# STM32F103T8.net
KiCad netlist of a schematic drawn in Altium Designer
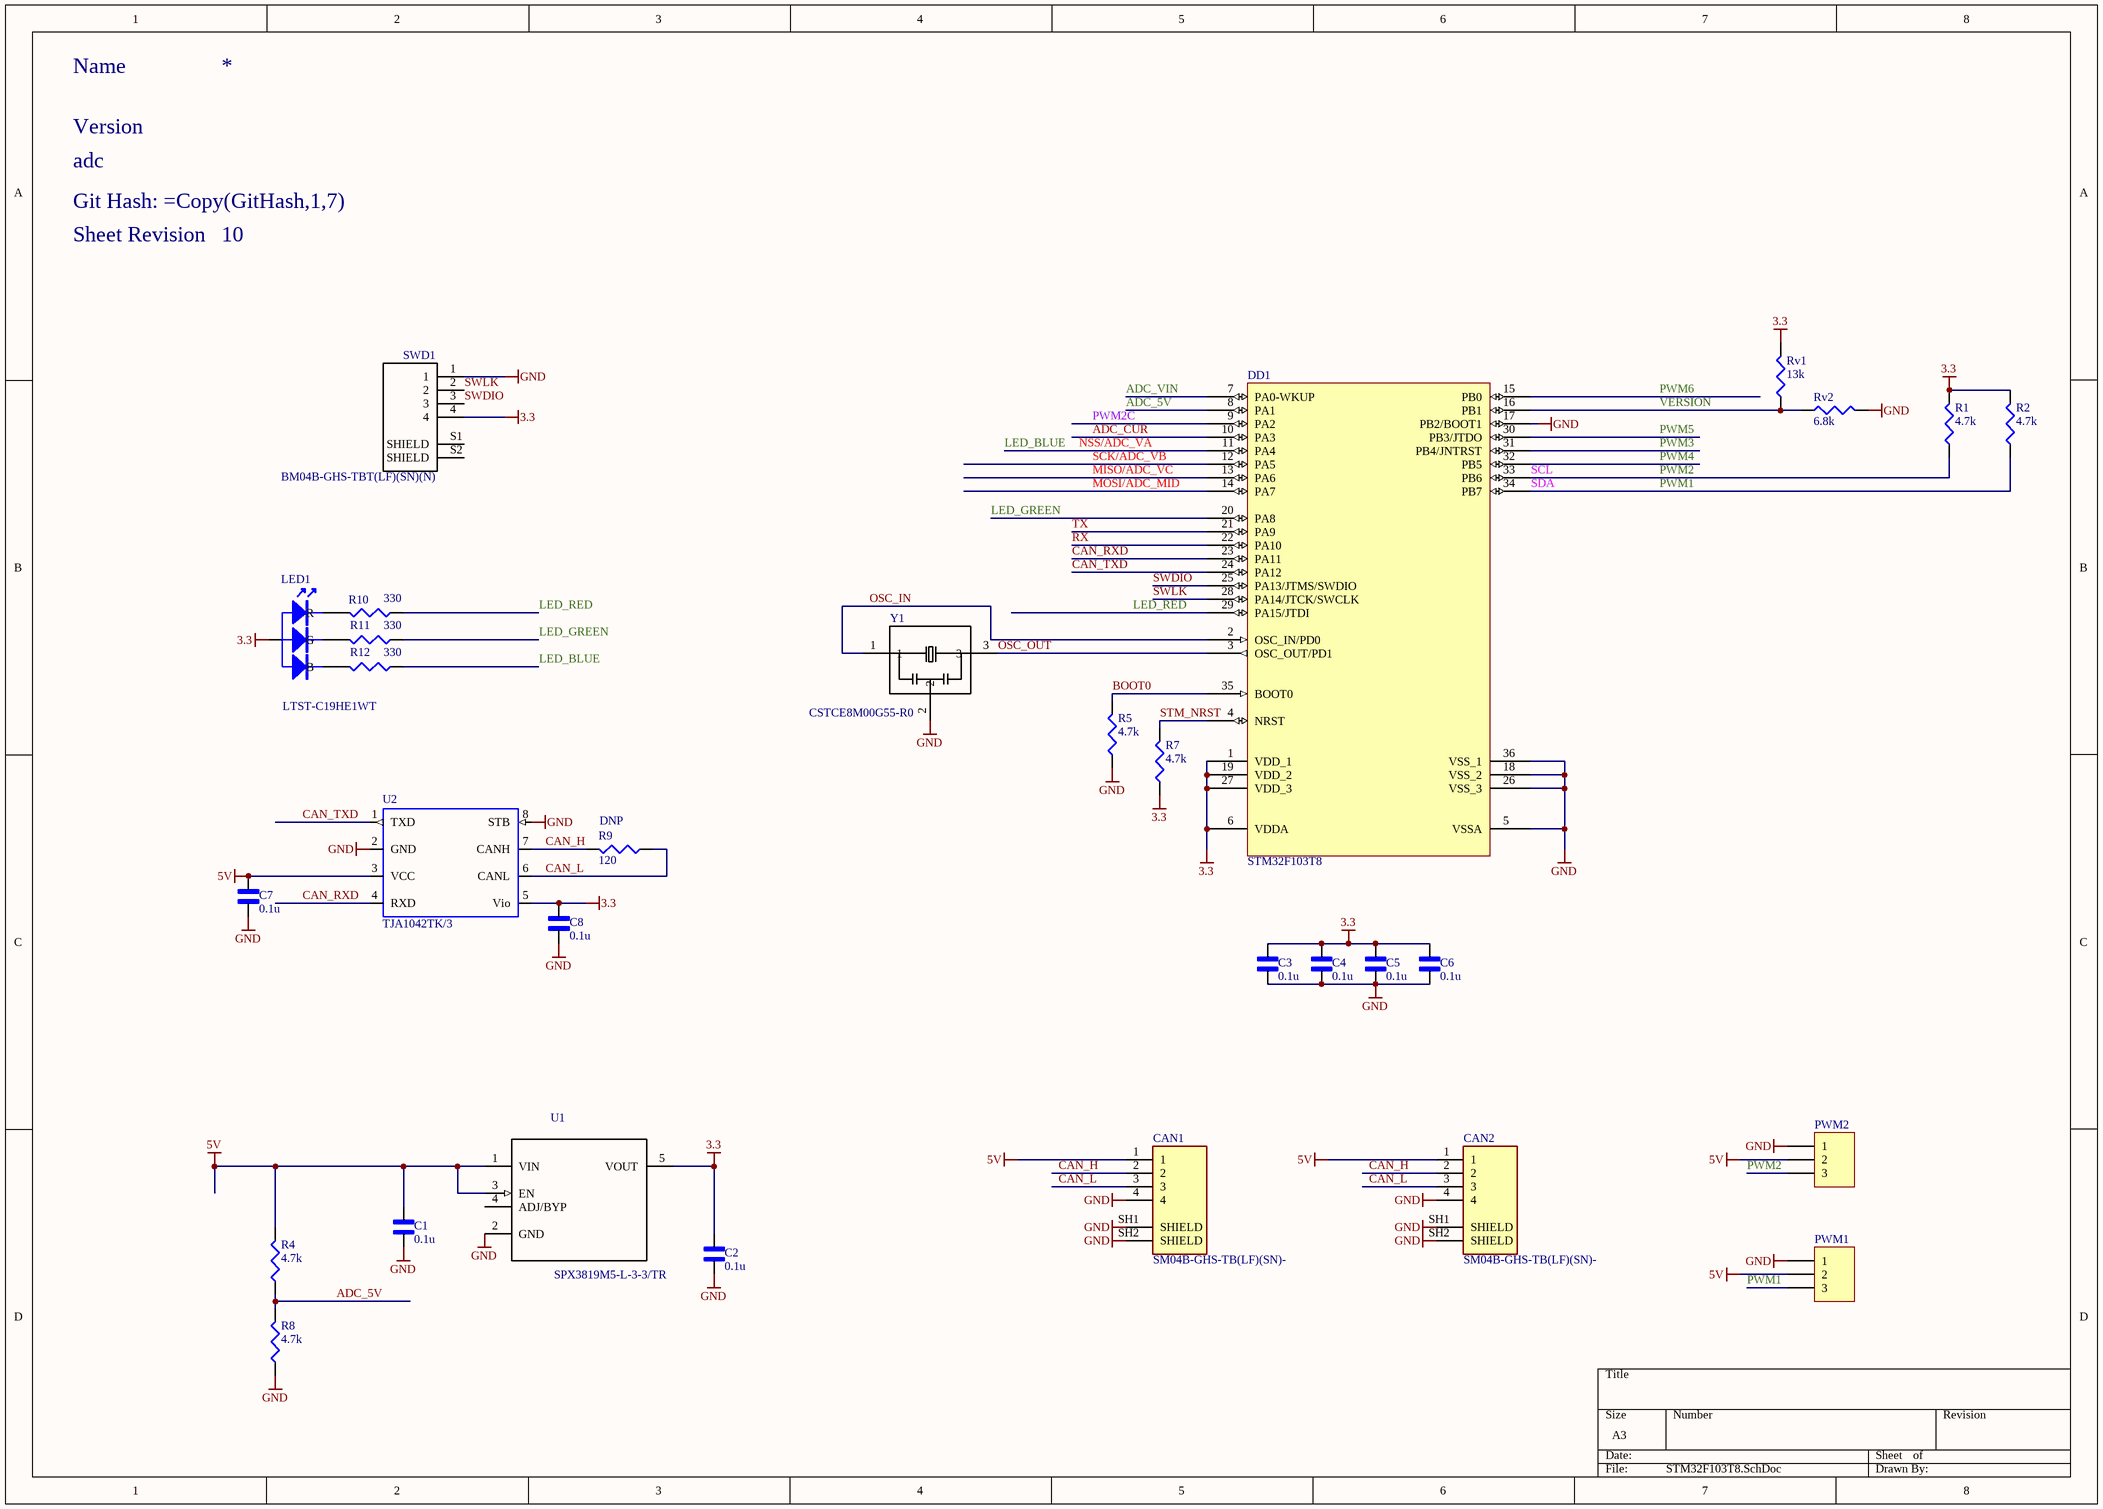
[diagram p0: STM32F103T8.SchDoc]

(export (version "E")
  (design (tool "Eeschema 10.0.6"))
  (components
    (comp (ref "C1")
      (value "0.1u")
      (footprint "CAPC1005X55N")
      (description "GCM155R71H104KE02D, Чип 0402 X7R 0.1uF +10% 50V,Конденсатор")
      (fields (field (name "MF") "Murata") (field (name "MP") "GCM155R71H104KE02D"))
      (libsource (lib "lib") (part "GCM155R71H104KE02D"))
    )
    (comp (ref "C2")
      (value "0.1u")
      (footprint "CAPC1005X55N")
      (description "GCM155R71H104KE02D, Чип 0402 X7R 0.1uF +10% 50V,Конденсатор")
      (fields (field (name "MF") "Murata") (field (name "MP") "GCM155R71H104KE02D"))
      (libsource (lib "lib") (part "GCM155R71H104KE02D"))
    )
    (comp (ref "C3")
      (value "0.1u")
      (footprint "CAPC1005X55N")
      (description "GCM155R71H104KE02D, Чип 0402 X7R 0.1uF +10% 50V,Конденсатор")
      (fields (field (name "MF") "Murata") (field (name "MP") "GCM155R71H104KE02D"))
      (libsource (lib "lib") (part "GCM155R71H104KE02D"))
    )
    (comp (ref "C4")
      (value "0.1u")
      (footprint "CAPC1005X55N")
      (description "GCM155R71H104KE02D, Чип 0402 X7R 0.1uF +10% 50V,Конденсатор")
      (fields (field (name "MF") "Murata") (field (name "MP") "GCM155R71H104KE02D"))
      (libsource (lib "lib") (part "GCM155R71H104KE02D"))
    )
    (comp (ref "C5")
      (value "0.1u")
      (footprint "CAPC1005X55N")
      (description "GCM155R71H104KE02D, Чип 0402 X7R 0.1uF +10% 50V,Конденсатор")
      (fields (field (name "MF") "Murata") (field (name "MP") "GCM155R71H104KE02D"))
      (libsource (lib "lib") (part "GCM155R71H104KE02D"))
    )
    (comp (ref "C6")
      (value "0.1u")
      (footprint "CAPC1005X55N")
      (description "GCM155R71H104KE02D, Чип 0402 X7R 0.1uF +10% 50V,Конденсатор")
      (fields (field (name "MF") "Murata") (field (name "MP") "GCM155R71H104KE02D"))
      (libsource (lib "lib") (part "GCM155R71H104KE02D"))
    )
    (comp (ref "C7")
      (value "0.1u")
      (footprint "CAPC1005X55N")
      (description "GCM155R71H104KE02D, Чип 0402 X7R 0.1uF +10% 50V,Конденсатор")
      (fields (field (name "MF") "Murata") (field (name "MP") "GCM155R71H104KE02D"))
      (libsource (lib "lib") (part "GCM155R71H104KE02D"))
    )
    (comp (ref "C8")
      (value "0.1u")
      (footprint "CAPC1005X55N")
      (description "GCM155R71H104KE02D, Чип 0402 X7R 0.1uF +10% 50V,Конденсатор")
      (fields (field (name "MF") "Murata") (field (name "MP") "GCM155R71H104KE02D"))
      (libsource (lib "lib") (part "GCM155R71H104KE02D"))
    )
    (comp (ref "CAN1")
      (value "SM04B-GHS-TB(LF)(SN)-")
      (footprint "JST_SM04B-GHS-TB(LF)(SN)-")
      (description "Connector Header Surface Mount, Right Angle 4 position 0.049 _1.25mm_")
      (fields (field (name "MP") "SM04B-GHS-TB(LF)(SN)") (field (name "MF") "JST Sales"))
      (libsource (lib "lib") (part "SM04B-GHS-TB(LF)(SN)-"))
    )
    (comp (ref "CAN2")
      (value "SM04B-GHS-TB(LF)(SN)-")
      (footprint "JST_SM04B-GHS-TB(LF)(SN)-")
      (description "Connector Header Surface Mount, Right Angle 4 position 0.049 _1.25mm_")
      (fields (field (name "MP") "SM04B-GHS-TB(LF)(SN)") (field (name "MF") "JST Sales"))
      (libsource (lib "lib") (part "SM04B-GHS-TB(LF)(SN)-"))
    )
    (comp (ref "DD1")
      (value "STM32F103T8")
      (footprint "*QFN50P600X600X100-37N")
      (description "STM32F103T8U6, Микроконтроллер 32BIT ARM 64K FLASH [VFQFPN-36]")
      (fields (field (name "MF") "STM") (field (name "MP") "STM32F103T8U6"))
      (libsource (lib "lib") (part "STM32F103T8"))
    )
    (comp (ref "LED1")
      (value "LTST-C19HE1WT")
      (footprint "LTST-C19HE1WT")
      (description "Blue/Green/Red")
      (libsource (lib "lib") (part "RGB_LED_5MM"))
    )
    (comp (ref "PWM1")
      (value "A")
      (footprint "HDR Side 3 pin")
      (description "Header, 3-Pin")
      (fields (field (name "MF") "Connfly electronic (Zhenqin)") (field (name "MP") "PLS-3 (DS1021-1x3)"))
      (libsource (lib "DC_DC") (part "Header 3"))
    )
    (comp (ref "PWM2")
      (value "A")
      (footprint "HDR Side 3 pin")
      (description "Header, 3-Pin")
      (fields (field (name "MF") "Connfly electronic (Zhenqin)") (field (name "MP") "PLS-3 (DS1021-1x3)"))
      (libsource (lib "DC_DC") (part "Header 3"))
    )
    (comp (ref "R1")
      (value "4.7k")
      (footprint "RESC1005X40N")
      (description "0.062Вт 0402 4.7 кОм, 1%, Чип резистор (SMD)")
      (fields (field (name "MF") "Yageo or NXP") (field (name "MP") "RC0402FR-074K7L"))
      (libsource (lib "lib") (part "RC0402FR-074K7L"))
    )
    (comp (ref "R2")
      (value "4.7k")
      (footprint "RESC1005X40N")
      (description "0.062Вт 0402 4.7 кОм, 1%, Чип резистор (SMD)")
      (fields (field (name "MF") "Yageo or NXP") (field (name "MP") "RC0402FR-074K7L"))
      (libsource (lib "lib") (part "RC0402FR-074K7L"))
    )
    (comp (ref "R4")
      (value "4.7k")
      (footprint "RESC1005X40N")
      (description "0.062Вт 0402 4.7 кОм, 1%, Чип резистор (SMD)")
      (fields (field (name "MF") "Yageo or NXP") (field (name "MP") "RC0402FR-074K7L"))
      (libsource (lib "lib") (part "RC0402FR-074K7L"))
    )
    (comp (ref "R5")
      (value "4.7k")
      (footprint "RESC1005X40N")
      (description "0.062Вт 0402 4.7 кОм, 1%, Чип резистор (SMD)")
      (fields (field (name "MF") "Yageo or NXP") (field (name "MP") "RC0402FR-074K7L"))
      (libsource (lib "lib") (part "RC0402FR-074K7L"))
    )
    (comp (ref "R7")
      (value "4.7k")
      (footprint "RESC1005X40N")
      (description "0.062Вт 0402 4.7 кОм, 1%, Чип резистор (SMD)")
      (fields (field (name "MF") "Yageo or NXP") (field (name "MP") "RC0402FR-074K7L"))
      (libsource (lib "lib") (part "RC0402FR-074K7L"))
    )
    (comp (ref "R8")
      (value "4.7k")
      (footprint "RESC1005X40N")
      (description "0.062Вт 0402 4.7 кОм, 1%, Чип резистор (SMD)")
      (fields (field (name "MF") "Yageo or NXP") (field (name "MP") "RC0402FR-074K7L"))
      (libsource (lib "lib") (part "RC0402FR-074K7L"))
    )
    (comp (ref "R9")
      (value "120")
      (footprint "J1-0603")
      (description "120 Ohms 1 0.1 W 1 10 W Chip Resistor 0603 1608 Metric Thick Film")
      (fields
        (field (name "INSTRUCTIONS") "DNP")
        (field (name "MP") "RC0603FR-07120RL")
        (field (name "Comment") "Res3")
      )
      (libsource (lib "Miscellaneous Devices") (part "Res3"))
    )
    (comp (ref "R10")
      (value "330")
      (footprint "RESC1005X40N")
      (description "0.062Вт 0402 330 Ом, 1%, Чип резистор (SMD)")
      (fields (field (name "MF") "Yageo or NXP") (field (name "MP") "RC0402FR-07330RL"))
      (libsource (lib "lib") (part "RC0402FR-07330RL"))
    )
    (comp (ref "R11")
      (value "330")
      (footprint "RESC1005X40N")
      (description "0.062Вт 0402 330 Ом, 1%, Чип резистор (SMD)")
      (fields (field (name "MF") "Yageo or NXP") (field (name "MP") "RC0402FR-07330RL"))
      (libsource (lib "lib") (part "RC0402FR-07330RL"))
    )
    (comp (ref "R12")
      (value "330")
      (footprint "RESC1005X40N")
      (description "0.062Вт 0402 330 Ом, 1%, Чип резистор (SMD)")
      (fields (field (name "MF") "Yageo or NXP") (field (name "MP") "RC0402FR-07330RL"))
      (libsource (lib "lib") (part "RC0402FR-07330RL"))
    )
    (comp (ref "Rv1")
      (value "13k")
      (footprint "RESC1005X40N")
      (description "0.062Вт 0402 13 кОм, 1%, Чип резистор (SMD)")
      (fields (field (name "MF") "Yageo or NXP") (field (name "MP") "RC0402FR-0713KL"))
      (libsource (lib "lib") (part "RC0402FR-0713KL"))
    )
    (comp (ref "Rv2")
      (value "6.8k")
      (footprint "RESC1005X40N")
      (description "0.062Вт 0402 6.8 кОм, 1%, Чип резистор (SMD)")
      (fields (field (name "MF") "Yageo or NXP") (field (name "MP") "RC0402FR-076K8L"))
      (libsource (lib "lib") (part "RC0402FR-076K8L"))
    )
    (comp (ref "SWD1")
      (value "BM04B-GHS-TBT(LF)(SN)(N)")
      (footprint "JST_BM04B-GHS-holes")
      (description "Conn Shrouded Header HDR 4 POS 1.25mm Solder ST SMD Reel")
      (fields (field (name "MF") "JST Sales") (field (name "MP") "SM04B-GHS-TB(LF)(SN)"))
      (libsource (lib "lib") (part "BM04B-GHS-TBT(LF)(SN)(N)"))
    )
    (comp (ref "U1")
      (value "SPX3819M5-L-3-3/TR")
      (footprint "*SOT95P280X145-5N")
      (description "Low Dropout Voltage Regulator, Adjustable 0.5A, В±1%, 2.5 to 16 Vin, 5-Pin SOT-23")
      (fields (field (name "MF") "MaxLinear, Inc."))
      (libsource (lib "DC_DC") (part "SPX3819M5-L"))
    )
    (comp (ref "U2")
      (value "TJA1042TK/3")
      (footprint "SOT782-1")
      (description "1/1 Transceiver Half CANbus 8-SO")
      (fields (field (name "MF") "NXP USA"))
      (libsource (lib "lib") (part "TJA1042TK/3"))
    )
    (comp (ref "Y1")
      (value "CSTCE8M00G55-R0")
      (footprint "*OSC_CSTCE8M00G55-R0")
      (description "Ceramic Resonator 8MHz ??0.5% _Tol_ ??0.2% _Stability_ 33pF 40Ohm 3-Pin CSMD T/R")
      (fields (field (name "MP") "CSTCE8M00G55-R0 or CSTCE8M00G52-R0") (field (name "MF") "Murata"))
      (libsource (lib "DC_DC") (part "CSTCE8M00G55-R0"))
    )
  )
  (nets
    (net (code "1") (name "/ADC_5V") (class "Default")
      (node (ref "DD1") (pin "8") (pinfunction "PA1_8") (pintype "bidirectional"))
      (node (ref "R4") (pin "1") (pinfunction "1_1") (pintype "passive"))
      (node (ref "R8") (pin "2") (pinfunction "2_2") (pintype "passive"))
    )
    (net (code "2") (name "/ADC_CUR") (class "Default")
      (node (ref "DD1") (pin "10") (pinfunction "PA3_10") (pintype "bidirectional"))
    )
    (net (code "3") (name "/ADC_VIN") (class "Default")
      (node (ref "DD1") (pin "7") (pinfunction "PA0-WKUP_7") (pintype "bidirectional"))
    )
    (net (code "4") (name "/BOOT0") (class "Default")
      (node (ref "DD1") (pin "35") (pinfunction "BOOT0_35") (pintype "input"))
      (node (ref "R5") (pin "2") (pinfunction "2_2") (pintype "passive"))
    )
    (net (code "5") (name "/CAN_H") (class "Default")
      (node (ref "CAN1") (pin "2") (pinfunction "2_2") (pintype "passive"))
      (node (ref "CAN2") (pin "2") (pinfunction "2_2") (pintype "passive"))
      (node (ref "R9") (pin "2") (pinfunction "2_2") (pintype "passive"))
      (node (ref "U2") (pin "7") (pinfunction "CANH_7") (pintype "bidirectional"))
    )
    (net (code "6") (name "/CAN_L") (class "Default")
      (node (ref "CAN1") (pin "3") (pinfunction "3_3") (pintype "passive"))
      (node (ref "CAN2") (pin "3") (pinfunction "3_3") (pintype "passive"))
      (node (ref "R9") (pin "1") (pinfunction "1_1") (pintype "passive"))
      (node (ref "U2") (pin "6") (pinfunction "CANL_6") (pintype "bidirectional"))
    )
    (net (code "7") (name "/CAN_RXD") (class "Default")
      (node (ref "DD1") (pin "23") (pinfunction "PA11_23") (pintype "bidirectional"))
      (node (ref "U2") (pin "4") (pinfunction "RXD_4") (pintype "bidirectional"))
    )
    (net (code "8") (name "/CAN_TXD") (class "Default")
      (node (ref "DD1") (pin "24") (pinfunction "PA12_24") (pintype "bidirectional"))
      (node (ref "U2") (pin "1") (pinfunction "TXD_1") (pintype "output"))
    )
    (net (code "9") (name "/LED_BLUE") (class "Default")
      (node (ref "DD1") (pin "11") (pinfunction "PA4_11") (pintype "bidirectional"))
      (node (ref "R12") (pin "1") (pinfunction "1_1") (pintype "passive"))
    )
    (net (code "10") (name "/LED_GREEN") (class "Default")
      (node (ref "DD1") (pin "20") (pinfunction "PA8_20") (pintype "bidirectional"))
      (node (ref "R11") (pin "1") (pinfunction "1_1") (pintype "passive"))
    )
    (net (code "11") (name "/LED_RED") (class "Default")
      (node (ref "DD1") (pin "29") (pinfunction "PA15/JTDI_29") (pintype "bidirectional"))
      (node (ref "R10") (pin "1") (pinfunction "1_1") (pintype "passive"))
    )
    (net (code "12") (name "/MISO{slash}ADC_VC") (class "Default")
      (node (ref "DD1") (pin "13") (pinfunction "PA6_13") (pintype "bidirectional"))
    )
    (net (code "13") (name "/MOSI{slash}ADC_MID") (class "Default")
      (node (ref "DD1") (pin "14") (pinfunction "PA7_14") (pintype "bidirectional"))
    )
    (net (code "14") (name "/OSC_IN") (class "Default")
      (node (ref "DD1") (pin "2") (pinfunction "OSC_IN/PD0_2") (pintype "input"))
      (node (ref "Y1") (pin "1") (pinfunction "1_1") (pintype "passive"))
    )
    (net (code "15") (name "/OSC_OUT") (class "Default")
      (node (ref "DD1") (pin "3") (pinfunction "OSC_OUT/PD1_3") (pintype "output"))
      (node (ref "Y1") (pin "3") (pinfunction "3_3") (pintype "passive"))
    )
    (net (code "16") (name "/PWM1") (class "Default")
      (node (ref "DD1") (pin "34") (pinfunction "PB7_34") (pintype "bidirectional"))
      (node (ref "PWM1") (pin "3") (pinfunction "3_3") (pintype "passive"))
      (node (ref "R2") (pin "1") (pinfunction "1_1") (pintype "passive"))
    )
    (net (code "17") (name "/PWM2") (class "Default")
      (node (ref "DD1") (pin "33") (pinfunction "PB6_33") (pintype "bidirectional"))
      (node (ref "PWM2") (pin "3") (pinfunction "3_3") (pintype "passive"))
      (node (ref "R1") (pin "1") (pinfunction "1_1") (pintype "passive"))
    )
    (net (code "18") (name "/PWM2C") (class "Default")
      (node (ref "DD1") (pin "9") (pinfunction "PA2_9") (pintype "bidirectional"))
    )
    (net (code "19") (name "/PWM3") (class "Default")
      (node (ref "DD1") (pin "31") (pinfunction "PB4/JNTRST_31") (pintype "bidirectional"))
    )
    (net (code "20") (name "/PWM4") (class "Default")
      (node (ref "DD1") (pin "32") (pinfunction "PB5_32") (pintype "bidirectional"))
    )
    (net (code "21") (name "/PWM5") (class "Default")
      (node (ref "DD1") (pin "30") (pinfunction "PB3/JTDO_30") (pintype "bidirectional"))
    )
    (net (code "22") (name "/PWM6") (class "Default")
      (node (ref "DD1") (pin "15") (pinfunction "PB0_15") (pintype "bidirectional"))
    )
    (net (code "23") (name "/RX") (class "Default")
      (node (ref "DD1") (pin "22") (pinfunction "PA10_22") (pintype "bidirectional"))
    )
    (net (code "24") (name "/SCK{slash}ADC_VB") (class "Default")
      (node (ref "DD1") (pin "12") (pinfunction "PA5_12") (pintype "bidirectional"))
    )
    (net (code "25") (name "/STM_NRST") (class "Default")
      (node (ref "DD1") (pin "4") (pinfunction "NRST_4") (pintype "bidirectional"))
      (node (ref "R7") (pin "2") (pinfunction "2_2") (pintype "passive"))
    )
    (net (code "26") (name "/SWDIO") (class "Default")
      (node (ref "DD1") (pin "25") (pinfunction "PA13/JTMS/SWDIO_25") (pintype "bidirectional"))
      (node (ref "SWD1") (pin "3") (pinfunction "3_3") (pintype "passive"))
    )
    (net (code "27") (name "/SWLK") (class "Default")
      (node (ref "DD1") (pin "28") (pinfunction "PA14/JTCK/SWCLK_28") (pintype "bidirectional"))
      (node (ref "SWD1") (pin "2") (pinfunction "2_2") (pintype "passive"))
    )
    (net (code "28") (name "/TX") (class "Default")
      (node (ref "DD1") (pin "21") (pinfunction "PA9_21") (pintype "bidirectional"))
    )
    (net (code "29") (name "/VERSION") (class "Default")
      (node (ref "DD1") (pin "16") (pinfunction "PB1_16") (pintype "bidirectional"))
      (node (ref "Rv1") (pin "1") (pinfunction "1_1") (pintype "passive"))
      (node (ref "Rv2") (pin "1") (pinfunction "1_1") (pintype "passive"))
    )
    (net (code "30") (name "3.3") (class "Default")
      (node (ref "C2") (pin "2") (pinfunction "2_2") (pintype "passive"))
      (node (ref "C3") (pin "2") (pinfunction "2_2") (pintype "passive"))
      (node (ref "C4") (pin "2") (pinfunction "2_2") (pintype "passive"))
      (node (ref "C5") (pin "2") (pinfunction "2_2") (pintype "passive"))
      (node (ref "C6") (pin "2") (pinfunction "2_2") (pintype "passive"))
      (node (ref "C8") (pin "2") (pinfunction "2_2") (pintype "passive"))
      (node (ref "DD1") (pin "1") (pinfunction "VDD_1_1") (pintype "power_in"))
      (node (ref "DD1") (pin "19") (pinfunction "VDD_2_19") (pintype "power_in"))
      (node (ref "DD1") (pin "27") (pinfunction "VDD_3_27") (pintype "power_in"))
      (node (ref "DD1") (pin "6") (pinfunction "VDDA_6") (pintype "power_in"))
      (node (ref "LED1") (pin "4") (pinfunction "A_4") (pintype "passive"))
      (node (ref "R1") (pin "2") (pinfunction "2_2") (pintype "passive"))
      (node (ref "R2") (pin "2") (pinfunction "2_2") (pintype "passive"))
      (node (ref "R7") (pin "1") (pinfunction "1_1") (pintype "passive"))
      (node (ref "Rv1") (pin "2") (pinfunction "2_2") (pintype "passive"))
      (node (ref "SWD1") (pin "4") (pinfunction "4_4") (pintype "passive"))
      (node (ref "U1") (pin "5") (pinfunction "VOUT_5") (pintype "power_in"))
      (node (ref "U2") (pin "5") (pinfunction "Vio_5") (pintype "power_in"))
    )
    (net (code "31") (name "5V") (class "Default")
      (node (ref "C1") (pin "2") (pinfunction "2_2") (pintype "passive"))
      (node (ref "C7") (pin "2") (pinfunction "2_2") (pintype "passive"))
      (node (ref "CAN1") (pin "1") (pinfunction "1_1") (pintype "passive"))
      (node (ref "CAN2") (pin "1") (pinfunction "1_1") (pintype "passive"))
      (node (ref "PWM1") (pin "2") (pinfunction "2_2") (pintype "passive"))
      (node (ref "PWM2") (pin "2") (pinfunction "2_2") (pintype "passive"))
      (node (ref "R4") (pin "2") (pinfunction "2_2") (pintype "passive"))
      (node (ref "U1") (pin "1") (pinfunction "VIN_1") (pintype "power_in"))
      (node (ref "U1") (pin "3") (pinfunction "EN_3") (pintype "input"))
      (node (ref "U2") (pin "3") (pinfunction "VCC_3") (pintype "power_in"))
    )
    (net (code "32") (name "GND") (class "Default")
      (node (ref "C1") (pin "1") (pinfunction "1_1") (pintype "passive"))
      (node (ref "C2") (pin "1") (pinfunction "1_1") (pintype "passive"))
      (node (ref "C3") (pin "1") (pinfunction "1_1") (pintype "passive"))
      (node (ref "C4") (pin "1") (pinfunction "1_1") (pintype "passive"))
      (node (ref "C5") (pin "1") (pinfunction "1_1") (pintype "passive"))
      (node (ref "C6") (pin "1") (pinfunction "1_1") (pintype "passive"))
      (node (ref "C7") (pin "1") (pinfunction "1_1") (pintype "passive"))
      (node (ref "C8") (pin "1") (pinfunction "1_1") (pintype "passive"))
      (node (ref "CAN1") (pin "4") (pinfunction "4_4") (pintype "passive"))
      (node (ref "CAN1") (pin "SH1") (pinfunction "SHIELD_SH1") (pintype "power_in"))
      (node (ref "CAN1") (pin "SH2") (pinfunction "SHIELD_SH2") (pintype "power_in"))
      (node (ref "CAN2") (pin "4") (pinfunction "4_4") (pintype "passive"))
      (node (ref "CAN2") (pin "SH1") (pinfunction "SHIELD_SH1") (pintype "power_in"))
      (node (ref "CAN2") (pin "SH2") (pinfunction "SHIELD_SH2") (pintype "power_in"))
      (node (ref "DD1") (pin "17") (pinfunction "PB2/BOOT1_17") (pintype "bidirectional"))
      (node (ref "DD1") (pin "18") (pinfunction "VSS_2_18") (pintype "power_in"))
      (node (ref "DD1") (pin "26") (pinfunction "VSS_3_26") (pintype "power_in"))
      (node (ref "DD1") (pin "36") (pinfunction "VSS_1_36") (pintype "power_in"))
      (node (ref "DD1") (pin "5") (pinfunction "VSSA_5") (pintype "power_in"))
      (node (ref "PWM1") (pin "1") (pinfunction "1_1") (pintype "passive"))
      (node (ref "PWM2") (pin "1") (pinfunction "1_1") (pintype "passive"))
      (node (ref "R5") (pin "1") (pinfunction "1_1") (pintype "passive"))
      (node (ref "R8") (pin "1") (pinfunction "1_1") (pintype "passive"))
      (node (ref "Rv2") (pin "2") (pinfunction "2_2") (pintype "passive"))
      (node (ref "SWD1") (pin "1") (pinfunction "1_1") (pintype "passive"))
      (node (ref "U1") (pin "2") (pinfunction "GND_2") (pintype "passive"))
      (node (ref "U2") (pin "2") (pinfunction "GND_2") (pintype "power_in"))
      (node (ref "U2") (pin "8") (pinfunction "STB_8") (pintype "input"))
      (node (ref "Y1") (pin "2") (pinfunction "2_2") (pintype "power_in"))
    )
    (net (code "33") (name "Net-(LED1-B)") (class "Default")
      (node (ref "LED1") (pin "3") (pinfunction "B_3") (pintype "passive"))
      (node (ref "R12") (pin "2") (pinfunction "2_2") (pintype "passive"))
    )
    (net (code "34") (name "Net-(LED1-G)") (class "Default")
      (node (ref "LED1") (pin "2") (pinfunction "G_2") (pintype "passive"))
      (node (ref "R11") (pin "2") (pinfunction "2_2") (pintype "passive"))
    )
    (net (code "35") (name "Net-(LED1-R)") (class "Default")
      (node (ref "LED1") (pin "1") (pinfunction "R_1") (pintype "passive"))
      (node (ref "R10") (pin "2") (pinfunction "2_2") (pintype "passive"))
    )
    (net (code "36") (name "unconnected-(SWD1-SHIELD-PadS1)") (class "Default")
      (node (ref "SWD1") (pin "S1") (pinfunction "SHIELD_S1") (pintype "passive"))
    )
    (net (code "37") (name "unconnected-(SWD1-SHIELD-PadS2)") (class "Default")
      (node (ref "SWD1") (pin "S2") (pinfunction "SHIELD_S2") (pintype "passive"))
    )
    (net (code "38") (name "unconnected-(U1-ADJ{slash}BYP-Pad4)") (class "Default")
      (node (ref "U1") (pin "4") (pinfunction "ADJ/BYP_4") (pintype "passive"))
    )
  )
)
